# Sheet1.net
KiCad netlist of a schematic drawn in Altium Designer
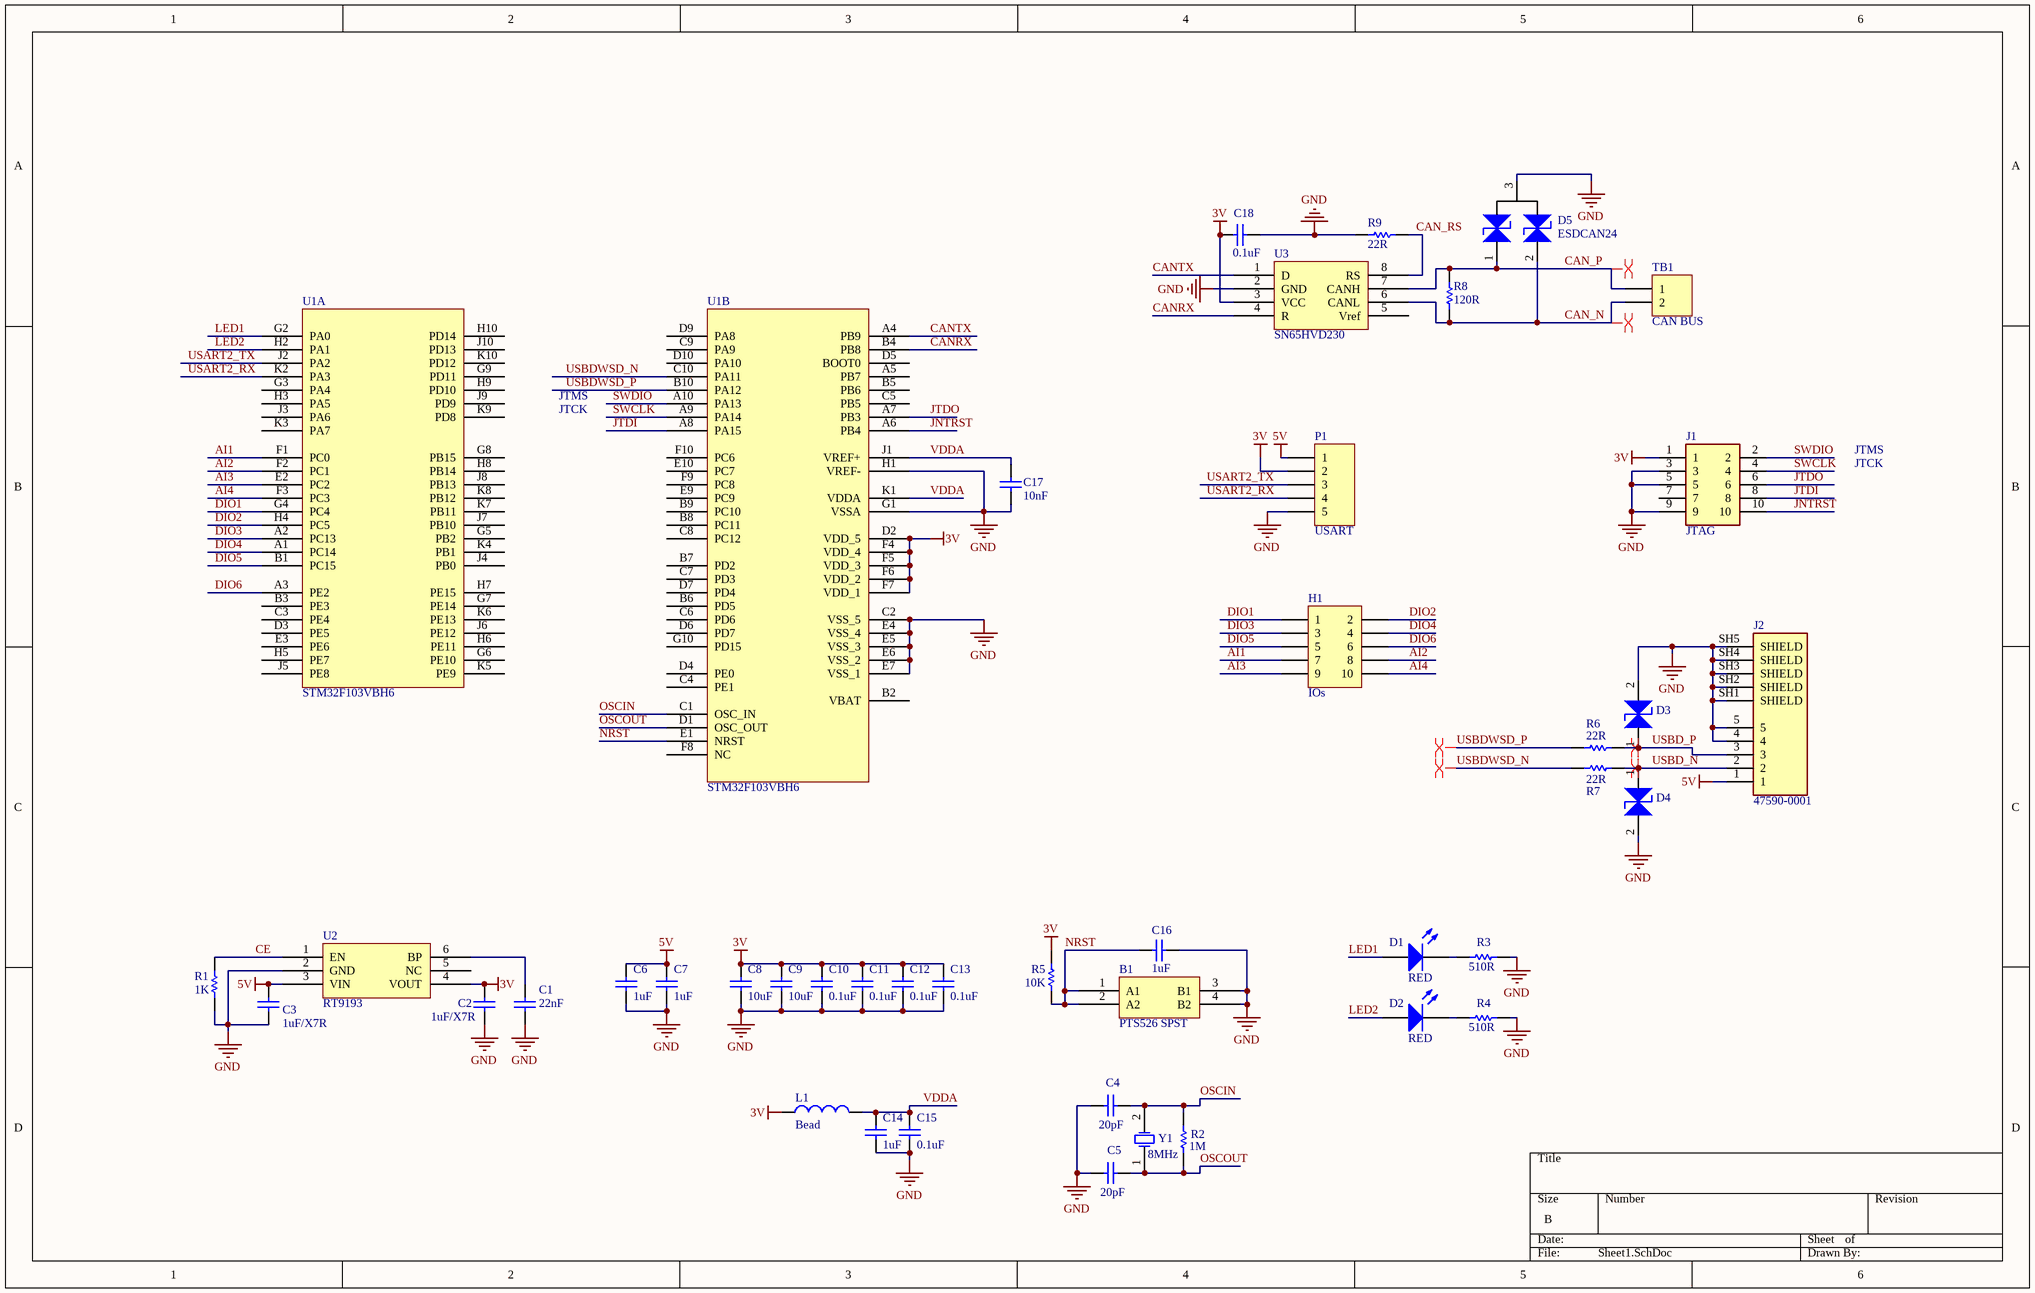
[diagram p0: Sheet1.SchDoc]

(export (version "E")
  (design (tool "Eeschema 10.0.6"))
  (components
    (comp (ref "B1")
      (value "PTS526 SPST")
      (footprint "PTS526 SPST")
      (libsource (lib "PCB_schm_lib") (part "PTS526 SPST"))
    )
    (comp (ref "C1")
      (value "22nF")
      (footprint "0603")
      (description "Capacitor")
      (fields (field (name "Comment") "Cap") (field (name "PUBLISHER") "Altium Limited"))
      (libsource (lib "Miscellaneous Devices") (part "Cap"))
    )
    (comp (ref "C2")
      (value "1uF/X7R")
      (footprint "0603")
      (description "Capacitor")
      (fields (field (name "Comment") "Cap") (field (name "PUBLISHER") "Altium Limited"))
      (libsource (lib "Miscellaneous Devices") (part "Cap"))
    )
    (comp (ref "C3")
      (value "1uF/X7R")
      (footprint "0603")
      (description "Capacitor")
      (fields (field (name "Comment") "Cap") (field (name "PUBLISHER") "Altium Limited"))
      (libsource (lib "Miscellaneous Devices") (part "Cap"))
    )
    (comp (ref "C4")
      (value "20pF")
      (footprint "0603")
      (description "Capacitor")
      (fields (field (name "Comment") "Cap") (field (name "PUBLISHER") "Altium Limited"))
      (libsource (lib "Miscellaneous Devices") (part "Cap"))
    )
    (comp (ref "C5")
      (value "20pF")
      (footprint "0603")
      (description "Capacitor")
      (fields (field (name "Comment") "Cap") (field (name "PUBLISHER") "Altium Limited"))
      (libsource (lib "Miscellaneous Devices") (part "Cap"))
    )
    (comp (ref "C6")
      (value "1uF")
      (footprint "0603")
      (description "Capacitor")
      (fields (field (name "Comment") "Cap") (field (name "PUBLISHER") "Altium Limited"))
      (libsource (lib "Miscellaneous Devices") (part "Cap"))
    )
    (comp (ref "C7")
      (value "1uF")
      (footprint "0603")
      (description "Capacitor")
      (fields (field (name "Comment") "Cap") (field (name "PUBLISHER") "Altium Limited"))
      (libsource (lib "Miscellaneous Devices") (part "Cap"))
    )
    (comp (ref "C8")
      (value "10uF")
      (footprint "0603")
      (description "Capacitor")
      (fields (field (name "Comment") "Cap") (field (name "PUBLISHER") "Altium Limited"))
      (libsource (lib "Miscellaneous Devices") (part "Cap"))
    )
    (comp (ref "C9")
      (value "10uF")
      (footprint "0603")
      (description "Capacitor")
      (fields (field (name "Comment") "Cap") (field (name "PUBLISHER") "Altium Limited"))
      (libsource (lib "Miscellaneous Devices") (part "Cap"))
    )
    (comp (ref "C10")
      (value "0.1uF")
      (footprint "0603")
      (description "Capacitor")
      (fields (field (name "Comment") "Cap") (field (name "PUBLISHER") "Altium Limited"))
      (libsource (lib "Miscellaneous Devices") (part "Cap"))
    )
    (comp (ref "C11")
      (value "0.1uF")
      (footprint "0603")
      (description "Capacitor")
      (fields (field (name "Comment") "Cap") (field (name "PUBLISHER") "Altium Limited"))
      (libsource (lib "Miscellaneous Devices") (part "Cap"))
    )
    (comp (ref "C12")
      (value "0.1uF")
      (footprint "0603")
      (description "Capacitor")
      (fields (field (name "Comment") "Cap") (field (name "PUBLISHER") "Altium Limited"))
      (libsource (lib "Miscellaneous Devices") (part "Cap"))
    )
    (comp (ref "C13")
      (value "0.1uF")
      (footprint "0603")
      (description "Capacitor")
      (fields (field (name "Comment") "Cap") (field (name "PUBLISHER") "Altium Limited"))
      (libsource (lib "Miscellaneous Devices") (part "Cap"))
    )
    (comp (ref "C14")
      (value "1uF")
      (footprint "0603")
      (description "Capacitor")
      (fields (field (name "Comment") "Cap") (field (name "PUBLISHER") "Altium Limited"))
      (libsource (lib "Miscellaneous Devices") (part "Cap"))
    )
    (comp (ref "C15")
      (value "0.1uF")
      (footprint "0603")
      (description "Capacitor")
      (fields (field (name "Comment") "Cap") (field (name "PUBLISHER") "Altium Limited"))
      (libsource (lib "Miscellaneous Devices") (part "Cap"))
    )
    (comp (ref "C16")
      (value "1uF")
      (footprint "0603")
      (description "Capacitor")
      (fields (field (name "Comment") "Cap") (field (name "PUBLISHER") "Altium Limited"))
      (libsource (lib "Miscellaneous Devices") (part "Cap"))
    )
    (comp (ref "C17")
      (value "10nF")
      (footprint "0603")
      (description "Capacitor")
      (fields (field (name "Comment") "Cap") (field (name "PUBLISHER") "Altium Limited"))
      (libsource (lib "Miscellaneous Devices") (part "Cap"))
    )
    (comp (ref "C18")
      (value "0.1uF")
      (footprint "0603")
      (description "Capacitor")
      (fields (field (name "Comment") "Cap") (field (name "PUBLISHER") "Altium Limited"))
      (libsource (lib "Miscellaneous Devices") (part "Cap"))
    )
    (comp (ref "D1")
      (value "RED")
      (footprint "0603")
      (description "Typical RED, GREEN, YELLOW, AMBER GaAs LED")
      (fields (field (name "PUBLISHER") "Altium Limited"))
      (libsource (lib "Miscellaneous Devices") (part "LED2"))
    )
    (comp (ref "D2")
      (value "RED")
      (footprint "0603")
      (description "Typical RED, GREEN, YELLOW, AMBER GaAs LED")
      (fields (field (name "PUBLISHER") "Altium Limited"))
      (libsource (lib "Miscellaneous Devices") (part "LED2"))
    )
    (comp (ref "D3") (value "TVS") (footprint "SOD323") (libsource (lib "PCB_schm_lib") (part "TVS")))
    (comp (ref "D4") (value "TVS") (footprint "SOD323") (libsource (lib "PCB_schm_lib") (part "TVS")))
    (comp (ref "D5")
      (value "ESDCAN24")
      (footprint "SOT-23")
      (libsource (lib "PCB_schm_lib") (part "ESDCAN24"))
    )
    (comp (ref "H1")
      (value "IOs")
      (footprint "5X2 HEADER 1.27mm")
      (description "Header, 5-Pin, Dual row")
      (fields (field (name "PUBLISHER") "Altium Limited"))
      (libsource (lib "Miscellaneous Connectors") (part "Header 5X2"))
    )
    (comp (ref "J1")
      (value "JTAG")
      (footprint "SAMTEC_FTSH-105-01-L-DV-K")
      (description "Connector Header Surface Mount 10 position 0.050 _1.27mm_")
      (fields (field (name "MF") "Samtec") (field (name "MP") "FTSH-105-01-L-DV-K"))
      (libsource (lib "FTSH-105-01-L-DV-K") (part "FTSH-105-01-L-DV-K"))
    )
    (comp (ref "J2")
      (value "47590-0001")
      (footprint "MOLEX_47590-0001")
      (description "USB - micro AB Receptacle Connector 5 Position Surface Mount, Right Angle; Through Hole")
      (fields (field (name "MF") "Molex"))
      (libsource (lib "47590-0001") (part "47590-0001"))
    )
    (comp (ref "L1")
      (value "Bead")
      (footprint "0603")
      (description "Inductor")
      (fields (field (name "PUBLISHER") "Altium Limited"))
      (libsource (lib "Miscellaneous Devices") (part "Inductor"))
    )
    (comp (ref "P1")
      (value "USART")
      (footprint "5 Pin header 1.27mm")
      (description "Header, 5-Pin")
      (fields (field (name "PUBLISHER") "Altium Limited"))
      (libsource (lib "Miscellaneous Connectors") (part "Header 5"))
    )
    (comp (ref "R1")
      (value "1K")
      (footprint "0603")
      (description "Resistor")
      (fields (field (name "Comment") "Res1") (field (name "PUBLISHER") "Altium Limited"))
      (libsource (lib "Miscellaneous Devices") (part "Res1"))
    )
    (comp (ref "R2")
      (value "1M")
      (footprint "0603")
      (description "Resistor")
      (fields (field (name "Comment") "Res1") (field (name "PUBLISHER") "Altium Limited"))
      (libsource (lib "Miscellaneous Devices") (part "Res1"))
    )
    (comp (ref "R3")
      (value "510R")
      (footprint "0603")
      (description "Resistor")
      (fields (field (name "Comment") "Res1") (field (name "PUBLISHER") "Altium Limited"))
      (libsource (lib "Miscellaneous Devices") (part "Res1"))
    )
    (comp (ref "R4")
      (value "510R")
      (footprint "0603")
      (description "Resistor")
      (fields (field (name "Comment") "Res1") (field (name "PUBLISHER") "Altium Limited"))
      (libsource (lib "Miscellaneous Devices") (part "Res1"))
    )
    (comp (ref "R5")
      (value "10K")
      (footprint "0603")
      (description "Resistor")
      (fields (field (name "Comment") "Res1") (field (name "PUBLISHER") "Altium Limited"))
      (libsource (lib "Miscellaneous Devices") (part "Res1"))
    )
    (comp (ref "R6")
      (value "22R")
      (footprint "0603")
      (description "Resistor")
      (fields (field (name "Comment") "Res1") (field (name "PUBLISHER") "Altium Limited"))
      (libsource (lib "Miscellaneous Devices") (part "Res1"))
    )
    (comp (ref "R7")
      (value "22R")
      (footprint "0603")
      (description "Resistor")
      (fields (field (name "Comment") "Res1") (field (name "PUBLISHER") "Altium Limited"))
      (libsource (lib "Miscellaneous Devices") (part "Res1"))
    )
    (comp (ref "R8")
      (value "120R")
      (footprint "0603")
      (description "Resistor")
      (fields (field (name "Comment") "Res1") (field (name "PUBLISHER") "Altium Limited"))
      (libsource (lib "Miscellaneous Devices") (part "Res1"))
    )
    (comp (ref "R9")
      (value "22R")
      (footprint "0603")
      (description "Resistor")
      (fields (field (name "Comment") "Res1") (field (name "PUBLISHER") "Altium Limited"))
      (libsource (lib "Miscellaneous Devices") (part "Res1"))
    )
    (comp (ref "TB1")
      (value "CAN BUS")
      (footprint "Terminal Block 3.5mm")
      (description "Header, 2-Pin")
      (fields (field (name "PUBLISHER") "Altium Limited"))
      (libsource (lib "Miscellaneous Connectors") (part "Header 2"))
    )
    (comp (ref "U1")
      (value "STM32F103VBH6")
      (footprint "LFBGA100 10x10")
      (libsource (lib "PCB_schm_lib") (part "STM32F103VBH6"))
    )
    (comp (ref "U2") (value "RT9193") (footprint "WDFN-6L") (libsource (lib "PCB_schm_lib") (part "RT9193")))
    (comp (ref "U3")
      (value "SN65HVD230")
      (footprint "SOIC 8 1.27mm")
      (libsource (lib "PCB_schm_lib") (part "SN65HVD230"))
    )
    (comp (ref "Y1")
      (value "8MHz")
      (footprint "HC-49/US")
      (description "Crystal Oscillator")
      (fields (field (name "PUBLISHER") "Altium Limited"))
      (libsource (lib "Miscellaneous Devices") (part "XTAL"))
    )
  )
  (nets
    (net (code "1") (name "/AI1") (class "Default")
      (node (ref "H1") (pin "7") (pinfunction "7_7") (pintype "passive"))
      (node (ref "U1") (pin "F1") (pinfunction "PC0_F1") (pintype "passive"))
    )
    (net (code "2") (name "/AI2") (class "Default")
      (node (ref "H1") (pin "8") (pinfunction "8_8") (pintype "passive"))
      (node (ref "U1") (pin "F2") (pinfunction "PC1_F2") (pintype "passive"))
    )
    (net (code "3") (name "/AI3") (class "Default")
      (node (ref "H1") (pin "9") (pinfunction "9_9") (pintype "passive"))
      (node (ref "U1") (pin "E2") (pinfunction "PC2_E2") (pintype "passive"))
    )
    (net (code "4") (name "/AI4") (class "Default")
      (node (ref "H1") (pin "10") (pinfunction "10_10") (pintype "passive"))
      (node (ref "U1") (pin "F3") (pinfunction "PC3_F3") (pintype "passive"))
    )
    (net (code "5") (name "/CANRX") (class "Default")
      (node (ref "U1") (pin "B4") (pinfunction "PB8_B4") (pintype "passive"))
      (node (ref "U3") (pin "4") (pinfunction "R_4") (pintype "passive"))
    )
    (net (code "6") (name "/CANTX") (class "Default")
      (node (ref "U1") (pin "A4") (pinfunction "PB9_A4") (pintype "passive"))
      (node (ref "U3") (pin "1") (pinfunction "D_1") (pintype "passive"))
    )
    (net (code "7") (name "/CAN_N") (class "Default")
      (node (ref "D5") (pin "2") (pinfunction "K23_2") (pintype "passive"))
      (node (ref "R8") (pin "1") (pinfunction "1_1") (pintype "passive"))
      (node (ref "TB1") (pin "2") (pinfunction "2_2") (pintype "passive"))
      (node (ref "U3") (pin "6") (pinfunction "CANL_6") (pintype "passive"))
    )
    (net (code "8") (name "/CAN_P") (class "Default")
      (node (ref "D5") (pin "1") (pinfunction "K23_1") (pintype "passive"))
      (node (ref "R8") (pin "2") (pinfunction "2_2") (pintype "passive"))
      (node (ref "TB1") (pin "1") (pinfunction "1_1") (pintype "passive"))
      (node (ref "U3") (pin "7") (pinfunction "CANH_7") (pintype "passive"))
    )
    (net (code "9") (name "/CAN_RS") (class "Default")
      (node (ref "R9") (pin "1") (pinfunction "1_1") (pintype "passive"))
      (node (ref "U3") (pin "8") (pinfunction "RS_8") (pintype "passive"))
    )
    (net (code "10") (name "/CE") (class "Default")
      (node (ref "R1") (pin "2") (pinfunction "2_2") (pintype "passive"))
      (node (ref "U2") (pin "1") (pinfunction "EN_1") (pintype "passive"))
    )
    (net (code "11") (name "/DIO1") (class "Default")
      (node (ref "H1") (pin "1") (pinfunction "1_1") (pintype "passive"))
      (node (ref "U1") (pin "G4") (pinfunction "PC4_G4") (pintype "passive"))
    )
    (net (code "12") (name "/DIO2") (class "Default")
      (node (ref "H1") (pin "2") (pinfunction "2_2") (pintype "passive"))
      (node (ref "U1") (pin "H4") (pinfunction "PC5_H4") (pintype "passive"))
    )
    (net (code "13") (name "/DIO3") (class "Default")
      (node (ref "H1") (pin "3") (pinfunction "3_3") (pintype "passive"))
      (node (ref "U1") (pin "A2") (pinfunction "PC13_A2") (pintype "passive"))
    )
    (net (code "14") (name "/DIO4") (class "Default")
      (node (ref "H1") (pin "4") (pinfunction "4_4") (pintype "passive"))
      (node (ref "U1") (pin "A1") (pinfunction "PC14_A1") (pintype "passive"))
    )
    (net (code "15") (name "/DIO5") (class "Default")
      (node (ref "H1") (pin "5") (pinfunction "5_5") (pintype "passive"))
      (node (ref "U1") (pin "B1") (pinfunction "PC15_B1") (pintype "passive"))
    )
    (net (code "16") (name "/DIO6") (class "Default")
      (node (ref "H1") (pin "6") (pinfunction "6_6") (pintype "passive"))
      (node (ref "U1") (pin "A3") (pinfunction "PE2_A3") (pintype "passive"))
    )
    (net (code "17") (name "/JNTRST") (class "Default")
      (node (ref "J1") (pin "10") (pinfunction "10_10") (pintype "passive"))
      (node (ref "U1") (pin "A6") (pinfunction "PB4_A6") (pintype "passive"))
    )
    (net (code "18") (name "/JTDI") (class "Default")
      (node (ref "J1") (pin "8") (pinfunction "8_8") (pintype "passive"))
      (node (ref "U1") (pin "A8") (pinfunction "PA15_A8") (pintype "passive"))
    )
    (net (code "19") (name "/JTDO") (class "Default")
      (node (ref "J1") (pin "6") (pinfunction "6_6") (pintype "passive"))
      (node (ref "U1") (pin "A7") (pinfunction "PB3_A7") (pintype "passive"))
    )
    (net (code "20") (name "/LED1") (class "Default")
      (node (ref "D1") (pin "1") (pinfunction "A_1") (pintype "passive"))
      (node (ref "U1") (pin "G2") (pinfunction "PA0_G2") (pintype "passive"))
    )
    (net (code "21") (name "/LED2") (class "Default")
      (node (ref "D2") (pin "1") (pinfunction "A_1") (pintype "passive"))
      (node (ref "U1") (pin "H2") (pinfunction "PA1_H2") (pintype "passive"))
    )
    (net (code "22") (name "/NRST") (class "Default")
      (node (ref "B1") (pin "1") (pinfunction "A1_1") (pintype "passive"))
      (node (ref "B1") (pin "2") (pinfunction "A2_2") (pintype "passive"))
      (node (ref "C16") (pin "1") (pinfunction "1_1") (pintype "passive"))
      (node (ref "R5") (pin "2") (pinfunction "2_2") (pintype "passive"))
      (node (ref "U1") (pin "E1") (pinfunction "NRST_E1") (pintype "passive"))
    )
    (net (code "23") (name "/OSCIN") (class "Default")
      (node (ref "C4") (pin "2") (pinfunction "2_2") (pintype "passive"))
      (node (ref "R2") (pin "2") (pinfunction "2_2") (pintype "passive"))
      (node (ref "U1") (pin "C1") (pinfunction "OSC_IN_C1") (pintype "passive"))
      (node (ref "Y1") (pin "2") (pinfunction "OSC2_2") (pintype "passive"))
    )
    (net (code "24") (name "/OSCOUT") (class "Default")
      (node (ref "C5") (pin "2") (pinfunction "2_2") (pintype "passive"))
      (node (ref "R2") (pin "1") (pinfunction "1_1") (pintype "passive"))
      (node (ref "U1") (pin "D1") (pinfunction "OSC_OUT_D1") (pintype "passive"))
      (node (ref "Y1") (pin "1") (pinfunction "OSC1_1") (pintype "passive"))
    )
    (net (code "25") (name "/SWCLK") (class "Default")
      (node (ref "J1") (pin "4") (pinfunction "4_4") (pintype "passive"))
      (node (ref "U1") (pin "A9") (pinfunction "PA14_A9") (pintype "passive"))
    )
    (net (code "26") (name "/SWDIO") (class "Default")
      (node (ref "J1") (pin "2") (pinfunction "2_2") (pintype "passive"))
      (node (ref "U1") (pin "A10") (pinfunction "PA13_A10") (pintype "passive"))
    )
    (net (code "27") (name "/USART2_RX") (class "Default")
      (node (ref "P1") (pin "4") (pinfunction "4_4") (pintype "passive"))
      (node (ref "U1") (pin "K2") (pinfunction "PA3_K2") (pintype "passive"))
    )
    (net (code "28") (name "/USART2_TX") (class "Default")
      (node (ref "P1") (pin "3") (pinfunction "3_3") (pintype "passive"))
      (node (ref "U1") (pin "J2") (pinfunction "PA2_J2") (pintype "passive"))
    )
    (net (code "29") (name "/USBDWSD_N") (class "Default")
      (node (ref "R7") (pin "1") (pinfunction "1_1") (pintype "passive"))
      (node (ref "U1") (pin "C10") (pinfunction "PA11_C10") (pintype "passive"))
    )
    (net (code "30") (name "/USBDWSD_P") (class "Default")
      (node (ref "R6") (pin "1") (pinfunction "1_1") (pintype "passive"))
      (node (ref "U1") (pin "B10") (pinfunction "PA12_B10") (pintype "passive"))
    )
    (net (code "31") (name "/USBD_N") (class "Default")
      (node (ref "D4") (pin "1") (pinfunction "K23_1") (pintype "passive"))
      (node (ref "J2") (pin "2") (pinfunction "2_2") (pintype "passive"))
      (node (ref "R7") (pin "2") (pinfunction "2_2") (pintype "passive"))
    )
    (net (code "32") (name "/USBD_P") (class "Default")
      (node (ref "D3") (pin "1") (pinfunction "K23_1") (pintype "passive"))
      (node (ref "J2") (pin "3") (pinfunction "3_3") (pintype "passive"))
      (node (ref "R6") (pin "2") (pinfunction "2_2") (pintype "passive"))
    )
    (net (code "33") (name "/VDDA") (class "Default")
      (node (ref "C14") (pin "1") (pinfunction "1_1") (pintype "passive"))
      (node (ref "C15") (pin "1") (pinfunction "1_1") (pintype "passive"))
      (node (ref "C17") (pin "2") (pinfunction "2_2") (pintype "passive"))
      (node (ref "L1") (pin "2") (pinfunction "2_2") (pintype "passive"))
      (node (ref "U1") (pin "J1") (pinfunction "VREF+_J1") (pintype "passive"))
      (node (ref "U1") (pin "K1") (pinfunction "VDDA_K1") (pintype "passive"))
    )
    (net (code "34") (name "3V") (class "Default")
      (node (ref "C10") (pin "1") (pinfunction "1_1") (pintype "passive"))
      (node (ref "C11") (pin "1") (pinfunction "1_1") (pintype "passive"))
      (node (ref "C12") (pin "1") (pinfunction "1_1") (pintype "passive"))
      (node (ref "C13") (pin "1") (pinfunction "1_1") (pintype "passive"))
      (node (ref "C18") (pin "1") (pinfunction "1_1") (pintype "passive"))
      (node (ref "C2") (pin "1") (pinfunction "1_1") (pintype "passive"))
      (node (ref "C8") (pin "1") (pinfunction "1_1") (pintype "passive"))
      (node (ref "C9") (pin "1") (pinfunction "1_1") (pintype "passive"))
      (node (ref "J1") (pin "1") (pinfunction "1_1") (pintype "passive"))
      (node (ref "L1") (pin "1") (pinfunction "1_1") (pintype "passive"))
      (node (ref "P1") (pin "2") (pinfunction "2_2") (pintype "passive"))
      (node (ref "R5") (pin "1") (pinfunction "1_1") (pintype "passive"))
      (node (ref "U1") (pin "D2") (pinfunction "VDD_5_D2") (pintype "passive"))
      (node (ref "U1") (pin "F4") (pinfunction "VDD_4_F4") (pintype "passive"))
      (node (ref "U1") (pin "F5") (pinfunction "VDD_3_F5") (pintype "passive"))
      (node (ref "U1") (pin "F6") (pinfunction "VDD_2_F6") (pintype "passive"))
      (node (ref "U1") (pin "F7") (pinfunction "VDD_1_F7") (pintype "passive"))
      (node (ref "U2") (pin "4") (pinfunction "VOUT_4") (pintype "passive"))
      (node (ref "U3") (pin "3") (pinfunction "VCC_3") (pintype "passive"))
    )
    (net (code "35") (name "5V") (class "Default")
      (node (ref "C3") (pin "1") (pinfunction "1_1") (pintype "passive"))
      (node (ref "C6") (pin "1") (pinfunction "1_1") (pintype "passive"))
      (node (ref "C7") (pin "1") (pinfunction "1_1") (pintype "passive"))
      (node (ref "J2") (pin "1") (pinfunction "1_1") (pintype "passive"))
      (node (ref "P1") (pin "1") (pinfunction "1_1") (pintype "passive"))
      (node (ref "U2") (pin "3") (pinfunction "VIN_3") (pintype "passive"))
    )
    (net (code "36") (name "GND") (class "Default")
      (node (ref "B1") (pin "3") (pinfunction "B1_3") (pintype "passive"))
      (node (ref "B1") (pin "4") (pinfunction "B2_4") (pintype "passive"))
      (node (ref "C1") (pin "2") (pinfunction "2_2") (pintype "passive"))
      (node (ref "C10") (pin "2") (pinfunction "2_2") (pintype "passive"))
      (node (ref "C11") (pin "2") (pinfunction "2_2") (pintype "passive"))
      (node (ref "C12") (pin "2") (pinfunction "2_2") (pintype "passive"))
      (node (ref "C13") (pin "2") (pinfunction "2_2") (pintype "passive"))
      (node (ref "C14") (pin "2") (pinfunction "2_2") (pintype "passive"))
      (node (ref "C15") (pin "2") (pinfunction "2_2") (pintype "passive"))
      (node (ref "C16") (pin "2") (pinfunction "2_2") (pintype "passive"))
      (node (ref "C17") (pin "1") (pinfunction "1_1") (pintype "passive"))
      (node (ref "C18") (pin "2") (pinfunction "2_2") (pintype "passive"))
      (node (ref "C2") (pin "2") (pinfunction "2_2") (pintype "passive"))
      (node (ref "C3") (pin "2") (pinfunction "2_2") (pintype "passive"))
      (node (ref "C4") (pin "1") (pinfunction "1_1") (pintype "passive"))
      (node (ref "C5") (pin "1") (pinfunction "1_1") (pintype "passive"))
      (node (ref "C6") (pin "2") (pinfunction "2_2") (pintype "passive"))
      (node (ref "C7") (pin "2") (pinfunction "2_2") (pintype "passive"))
      (node (ref "C8") (pin "2") (pinfunction "2_2") (pintype "passive"))
      (node (ref "C9") (pin "2") (pinfunction "2_2") (pintype "passive"))
      (node (ref "D3") (pin "2") (pinfunction "K24_2") (pintype "passive"))
      (node (ref "D4") (pin "2") (pinfunction "K24_2") (pintype "passive"))
      (node (ref "D5") (pin "3") (pinfunction "K23_3") (pintype "passive"))
      (node (ref "J1") (pin "3") (pinfunction "3_3") (pintype "passive"))
      (node (ref "J1") (pin "5") (pinfunction "5_5") (pintype "passive"))
      (node (ref "J1") (pin "9") (pinfunction "9_9") (pintype "passive"))
      (node (ref "J2") (pin "4") (pinfunction "4_4") (pintype "passive"))
      (node (ref "J2") (pin "5") (pinfunction "5_5") (pintype "passive"))
      (node (ref "J2") (pin "SH1") (pinfunction "SHIELD_SH1") (pintype "passive"))
      (node (ref "J2") (pin "SH2") (pinfunction "SHIELD_SH2") (pintype "passive"))
      (node (ref "J2") (pin "SH3") (pinfunction "SHIELD_SH3") (pintype "passive"))
      (node (ref "J2") (pin "SH4") (pinfunction "SHIELD_SH4") (pintype "passive"))
      (node (ref "J2") (pin "SH5") (pinfunction "SHIELD_SH5") (pintype "passive"))
      (node (ref "P1") (pin "5") (pinfunction "5_5") (pintype "passive"))
      (node (ref "R1") (pin "1") (pinfunction "1_1") (pintype "passive"))
      (node (ref "R3") (pin "2") (pinfunction "2_2") (pintype "passive"))
      (node (ref "R4") (pin "2") (pinfunction "2_2") (pintype "passive"))
      (node (ref "R9") (pin "2") (pinfunction "2_2") (pintype "passive"))
      (node (ref "U1") (pin "C2") (pinfunction "VSS_5_C2") (pintype "passive"))
      (node (ref "U1") (pin "E4") (pinfunction "VSS_4_E4") (pintype "passive"))
      (node (ref "U1") (pin "E5") (pinfunction "VSS_3_E5") (pintype "passive"))
      (node (ref "U1") (pin "E6") (pinfunction "VSS_2_E6") (pintype "passive"))
      (node (ref "U1") (pin "E7") (pinfunction "VSS_1_E7") (pintype "passive"))
      (node (ref "U1") (pin "G1") (pinfunction "VSSA_G1") (pintype "passive"))
      (node (ref "U1") (pin "H1") (pinfunction "VREF-_H1") (pintype "passive"))
      (node (ref "U2") (pin "2") (pinfunction "GND_2") (pintype "passive"))
      (node (ref "U3") (pin "2") (pinfunction "GND_2") (pintype "passive"))
    )
    (net (code "37") (name "Net-(D1-K)") (class "Default")
      (node (ref "D1") (pin "2") (pinfunction "K_2") (pintype "passive"))
      (node (ref "R3") (pin "1") (pinfunction "1_1") (pintype "passive"))
    )
    (net (code "38") (name "Net-(D2-K)") (class "Default")
      (node (ref "D2") (pin "2") (pinfunction "K_2") (pintype "passive"))
      (node (ref "R4") (pin "1") (pinfunction "1_1") (pintype "passive"))
    )
    (net (code "39") (name "Net-(U2-BP)") (class "Default")
      (node (ref "C1") (pin "1") (pinfunction "1_1") (pintype "passive"))
      (node (ref "U2") (pin "6") (pinfunction "BP_6") (pintype "passive"))
    )
    (net (code "40") (name "unconnected-(J1-Pad7)") (class "Default")
      (node (ref "J1") (pin "7") (pinfunction "7_7") (pintype "passive"))
    )
    (net (code "41") (name "unconnected-(U1A-PA4-PadG3)") (class "Default")
      (node (ref "U1") (pin "G3") (pinfunction "PA4_G3") (pintype "passive"))
    )
    (net (code "42") (name "unconnected-(U1A-PA5-PadH3)") (class "Default")
      (node (ref "U1") (pin "H3") (pinfunction "PA5_H3") (pintype "passive"))
    )
    (net (code "43") (name "unconnected-(U1A-PA6-PadJ3)") (class "Default")
      (node (ref "U1") (pin "J3") (pinfunction "PA6_J3") (pintype "passive"))
    )
    (net (code "44") (name "unconnected-(U1A-PA7-PadK3)") (class "Default")
      (node (ref "U1") (pin "K3") (pinfunction "PA7_K3") (pintype "passive"))
    )
    (net (code "45") (name "unconnected-(U1A-PB0-PadJ4)") (class "Default")
      (node (ref "U1") (pin "J4") (pinfunction "PB0_J4") (pintype "passive"))
    )
    (net (code "46") (name "unconnected-(U1A-PB1-PadK4)") (class "Default")
      (node (ref "U1") (pin "K4") (pinfunction "PB1_K4") (pintype "passive"))
    )
    (net (code "47") (name "unconnected-(U1A-PB2-PadG5)") (class "Default")
      (node (ref "U1") (pin "G5") (pinfunction "PB2_G5") (pintype "passive"))
    )
    (net (code "48") (name "unconnected-(U1A-PB10-PadJ7)") (class "Default")
      (node (ref "U1") (pin "J7") (pinfunction "PB10_J7") (pintype "passive"))
    )
    (net (code "49") (name "unconnected-(U1A-PB11-PadK7)") (class "Default")
      (node (ref "U1") (pin "K7") (pinfunction "PB11_K7") (pintype "passive"))
    )
    (net (code "50") (name "unconnected-(U1A-PB12-PadK8)") (class "Default")
      (node (ref "U1") (pin "K8") (pinfunction "PB12_K8") (pintype "passive"))
    )
    (net (code "51") (name "unconnected-(U1A-PB13-PadJ8)") (class "Default")
      (node (ref "U1") (pin "J8") (pinfunction "PB13_J8") (pintype "passive"))
    )
    (net (code "52") (name "unconnected-(U1A-PB14-PadH8)") (class "Default")
      (node (ref "U1") (pin "H8") (pinfunction "PB14_H8") (pintype "passive"))
    )
    (net (code "53") (name "unconnected-(U1A-PB15-PadG8)") (class "Default")
      (node (ref "U1") (pin "G8") (pinfunction "PB15_G8") (pintype "passive"))
    )
    (net (code "54") (name "unconnected-(U1A-PD8-PadK9)") (class "Default")
      (node (ref "U1") (pin "K9") (pinfunction "PD8_K9") (pintype "passive"))
    )
    (net (code "55") (name "unconnected-(U1A-PD9-PadJ9)") (class "Default")
      (node (ref "U1") (pin "J9") (pinfunction "PD9_J9") (pintype "passive"))
    )
    (net (code "56") (name "unconnected-(U1A-PD10-PadH9)") (class "Default")
      (node (ref "U1") (pin "H9") (pinfunction "PD10_H9") (pintype "passive"))
    )
    (net (code "57") (name "unconnected-(U1A-PD11-PadG9)") (class "Default")
      (node (ref "U1") (pin "G9") (pinfunction "PD11_G9") (pintype "passive"))
    )
    (net (code "58") (name "unconnected-(U1A-PD12-PadK10)") (class "Default")
      (node (ref "U1") (pin "K10") (pinfunction "PD12_K10") (pintype "passive"))
    )
    (net (code "59") (name "unconnected-(U1A-PD13-PadJ10)") (class "Default")
      (node (ref "U1") (pin "J10") (pinfunction "PD13_J10") (pintype "passive"))
    )
    (net (code "60") (name "unconnected-(U1A-PD14-PadH10)") (class "Default")
      (node (ref "U1") (pin "H10") (pinfunction "PD14_H10") (pintype "passive"))
    )
    (net (code "61") (name "unconnected-(U1A-PE3-PadB3)") (class "Default")
      (node (ref "U1") (pin "B3") (pinfunction "PE3_B3") (pintype "passive"))
    )
    (net (code "62") (name "unconnected-(U1A-PE4-PadC3)") (class "Default")
      (node (ref "U1") (pin "C3") (pinfunction "PE4_C3") (pintype "passive"))
    )
    (net (code "63") (name "unconnected-(U1A-PE5-PadD3)") (class "Default")
      (node (ref "U1") (pin "D3") (pinfunction "PE5_D3") (pintype "passive"))
    )
    (net (code "64") (name "unconnected-(U1A-PE6-PadE3)") (class "Default")
      (node (ref "U1") (pin "E3") (pinfunction "PE6_E3") (pintype "passive"))
    )
    (net (code "65") (name "unconnected-(U1A-PE7-PadH5)") (class "Default")
      (node (ref "U1") (pin "H5") (pinfunction "PE7_H5") (pintype "passive"))
    )
    (net (code "66") (name "unconnected-(U1A-PE8-PadJ5)") (class "Default")
      (node (ref "U1") (pin "J5") (pinfunction "PE8_J5") (pintype "passive"))
    )
    (net (code "67") (name "unconnected-(U1A-PE9-PadK5)") (class "Default")
      (node (ref "U1") (pin "K5") (pinfunction "PE9_K5") (pintype "passive"))
    )
    (net (code "68") (name "unconnected-(U1A-PE10-PadG6)") (class "Default")
      (node (ref "U1") (pin "G6") (pinfunction "PE10_G6") (pintype "passive"))
    )
    (net (code "69") (name "unconnected-(U1A-PE11-PadH6)") (class "Default")
      (node (ref "U1") (pin "H6") (pinfunction "PE11_H6") (pintype "passive"))
    )
    (net (code "70") (name "unconnected-(U1A-PE12-PadJ6)") (class "Default")
      (node (ref "U1") (pin "J6") (pinfunction "PE12_J6") (pintype "passive"))
    )
    (net (code "71") (name "unconnected-(U1A-PE13-PadK6)") (class "Default")
      (node (ref "U1") (pin "K6") (pinfunction "PE13_K6") (pintype "passive"))
    )
    (net (code "72") (name "unconnected-(U1A-PE14-PadG7)") (class "Default")
      (node (ref "U1") (pin "G7") (pinfunction "PE14_G7") (pintype "passive"))
    )
    (net (code "73") (name "unconnected-(U1A-PE15-PadH7)") (class "Default")
      (node (ref "U1") (pin "H7") (pinfunction "PE15_H7") (pintype "passive"))
    )
    (net (code "74") (name "unconnected-(U1B-BOOT0-PadD5)") (class "Default")
      (node (ref "U1") (pin "D5") (pinfunction "BOOT0_D5") (pintype "passive"))
    )
    (net (code "75") (name "unconnected-(U1B-NC-PadF8)") (class "Default")
      (node (ref "U1") (pin "F8") (pinfunction "NC_F8") (pintype "passive"))
    )
    (net (code "76") (name "unconnected-(U1B-PA8-PadD9)") (class "Default")
      (node (ref "U1") (pin "D9") (pinfunction "PA8_D9") (pintype "passive"))
    )
    (net (code "77") (name "unconnected-(U1B-PA9-PadC9)") (class "Default")
      (node (ref "U1") (pin "C9") (pinfunction "PA9_C9") (pintype "passive"))
    )
    (net (code "78") (name "unconnected-(U1B-PA10-PadD10)") (class "Default")
      (node (ref "U1") (pin "D10") (pinfunction "PA10_D10") (pintype "passive"))
    )
    (net (code "79") (name "unconnected-(U1B-PB5-PadC5)") (class "Default")
      (node (ref "U1") (pin "C5") (pinfunction "PB5_C5") (pintype "passive"))
    )
    (net (code "80") (name "unconnected-(U1B-PB6-PadB5)") (class "Default")
      (node (ref "U1") (pin "B5") (pinfunction "PB6_B5") (pintype "passive"))
    )
    (net (code "81") (name "unconnected-(U1B-PB7-PadA5)") (class "Default")
      (node (ref "U1") (pin "A5") (pinfunction "PB7_A5") (pintype "passive"))
    )
    (net (code "82") (name "unconnected-(U1B-PC6-PadF10)") (class "Default")
      (node (ref "U1") (pin "F10") (pinfunction "PC6_F10") (pintype "passive"))
    )
    (net (code "83") (name "unconnected-(U1B-PC7-PadE10)") (class "Default")
      (node (ref "U1") (pin "E10") (pinfunction "PC7_E10") (pintype "passive"))
    )
    (net (code "84") (name "unconnected-(U1B-PC8-PadF9)") (class "Default")
      (node (ref "U1") (pin "F9") (pinfunction "PC8_F9") (pintype "passive"))
    )
    (net (code "85") (name "unconnected-(U1B-PC9-PadE9)") (class "Default")
      (node (ref "U1") (pin "E9") (pinfunction "PC9_E9") (pintype "passive"))
    )
    (net (code "86") (name "unconnected-(U1B-PC10-PadB9)") (class "Default")
      (node (ref "U1") (pin "B9") (pinfunction "PC10_B9") (pintype "passive"))
    )
    (net (code "87") (name "unconnected-(U1B-PC11-PadB8)") (class "Default")
      (node (ref "U1") (pin "B8") (pinfunction "PC11_B8") (pintype "passive"))
    )
    (net (code "88") (name "unconnected-(U1B-PC12-PadC8)") (class "Default")
      (node (ref "U1") (pin "C8") (pinfunction "PC12_C8") (pintype "passive"))
    )
    (net (code "89") (name "unconnected-(U1B-PD2-PadB7)") (class "Default")
      (node (ref "U1") (pin "B7") (pinfunction "PD2_B7") (pintype "passive"))
    )
    (net (code "90") (name "unconnected-(U1B-PD3-PadC7)") (class "Default")
      (node (ref "U1") (pin "C7") (pinfunction "PD3_C7") (pintype "passive"))
    )
    (net (code "91") (name "unconnected-(U1B-PD4-PadD7)") (class "Default")
      (node (ref "U1") (pin "D7") (pinfunction "PD4_D7") (pintype "passive"))
    )
    (net (code "92") (name "unconnected-(U1B-PD5-PadB6)") (class "Default")
      (node (ref "U1") (pin "B6") (pinfunction "PD5_B6") (pintype "passive"))
    )
    (net (code "93") (name "unconnected-(U1B-PD6-PadC6)") (class "Default")
      (node (ref "U1") (pin "C6") (pinfunction "PD6_C6") (pintype "passive"))
    )
    (net (code "94") (name "unconnected-(U1B-PD7-PadD6)") (class "Default")
      (node (ref "U1") (pin "D6") (pinfunction "PD7_D6") (pintype "passive"))
    )
    (net (code "95") (name "unconnected-(U1B-PD15-PadG10)") (class "Default")
      (node (ref "U1") (pin "G10") (pinfunction "PD15_G10") (pintype "passive"))
    )
    (net (code "96") (name "unconnected-(U1B-PE0-PadD4)") (class "Default")
      (node (ref "U1") (pin "D4") (pinfunction "PE0_D4") (pintype "passive"))
    )
    (net (code "97") (name "unconnected-(U1B-PE1-PadC4)") (class "Default")
      (node (ref "U1") (pin "C4") (pinfunction "PE1_C4") (pintype "passive"))
    )
    (net (code "98") (name "unconnected-(U1B-VBAT-PadB2)") (class "Default")
      (node (ref "U1") (pin "B2") (pinfunction "VBAT_B2") (pintype "passive"))
    )
    (net (code "99") (name "unconnected-(U2-NC-Pad5)") (class "Default")
      (node (ref "U2") (pin "5") (pinfunction "NC_5") (pintype "passive"))
    )
    (net (code "100") (name "unconnected-(U3-Vref-Pad5)") (class "Default")
      (node (ref "U3") (pin "5") (pinfunction "Vref_5") (pintype "passive"))
    )
  )
)
